# PM_proto_4.net
KiCad netlist of a schematic drawn in EAGLE
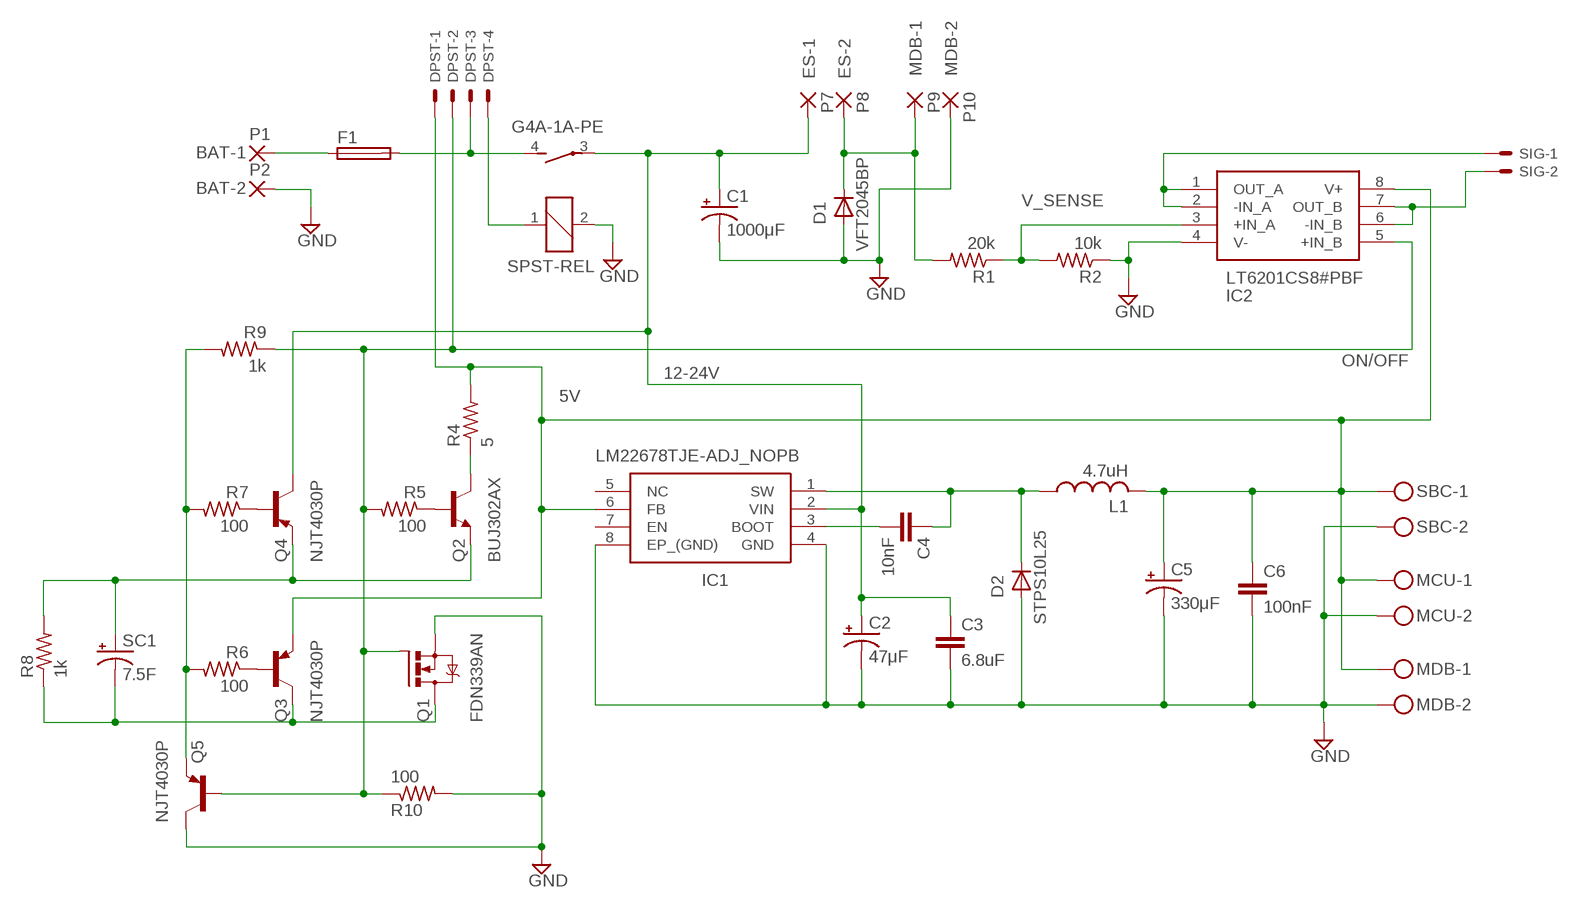
[diagram p0: schematic, sheet 1]

(export (version "E")
  (design (tool "Eeschema 10.0.6"))
  (components
    (comp (ref "C1")
      (value "1000μF")
      (footprint "eagle-import:E7,5-16")
      (libsource (lib "eagle-import") (part "CPOL-USE7.5-16"))
    )
    (comp (ref "C2")
      (value "47μF")
      (footprint "eagle-import:E2,5-6E")
      (libsource (lib "eagle-import") (part "CPOL-USE2,5-6E"))
    )
    (comp (ref "C3")
      (value "6.8uF")
      (footprint "eagle-import:C025-024X044")
      (libsource (lib "eagle-import") (part "C-EU025-024X044"))
    )
    (comp (ref "C4")
      (value "10nF")
      (footprint "eagle-import:C025-024X044")
      (libsource (lib "eagle-import") (part "C-EU025-024X044"))
    )
    (comp (ref "C5")
      (value "330μF")
      (footprint "eagle-import:E2,5-6E")
      (libsource (lib "eagle-import") (part "CPOL-USE2,5-6E"))
    )
    (comp (ref "C6")
      (value "100nF")
      (footprint "eagle-import:C025-024X044")
      (libsource (lib "eagle-import") (part "C-EU025-024X044"))
    )
    (comp (ref "D1")
      (value "VFT2045BP")
      (footprint "eagle-import:VFT2045BP")
      (libsource (lib "eagle-import") (part "VFT2045BP"))
    )
    (comp (ref "D2")
      (value "STPS10L25")
      (footprint "eagle-import:VFT2045BP")
      (libsource (lib "eagle-import") (part "VFT2045BP"))
    )
    (comp (ref "DPST")
      (value "JST-XH-04-PIN-LONG-PAD")
      (footprint "eagle-import:JST-XH-04-PACKAGE-LONG-PAD")
      (libsource (lib "eagle-import") (part "JST-XH-04-PIN-LONG-PAD"))
    )
    (comp (ref "F1")
      (value "0297015FUSE")
      (footprint "eagle-import:0297015HOLDER")
      (libsource (lib "eagle-import") (part "0297015FUSE"))
    )
    (comp (ref "IC1")
      (value "LM22678TJE-ADJ_NOPB")
      (footprint "eagle-import:LM22678TJEADJNOPB")
      (fields
        (field (name "ARROW_PART_NUMBER") "LM22678TJE-ADJ/NOPB")
        (field (name "RS_PART_NUMBER") "1625056")
      )
      (libsource (lib "eagle-import") (part "LM22678TJE-ADJ_NOPB"))
    )
    (comp (ref "IC2")
      (value "LT6201CS8#PBF")
      (footprint "eagle-import:SOIC127P599X175-8N")
      (fields (field (name "RS_PART_NUMBER") "5061072P"))
      (libsource (lib "eagle-import") (part "LT6201CS8#PBF"))
    )
    (comp (ref "L1")
      (value "4.7uH")
      (footprint "eagle-import:6000-XXXX-RC")
      (libsource (lib "eagle-import") (part "L-US6000-XXX-RC"))
    )
    (comp (ref "MCU")
      (value "MKDSN1,5/2-5,08")
      (footprint "eagle-import:MKDSN1,5_2-5,08")
      (libsource (lib "eagle-import") (part "MKDSN1,5/2-5,08"))
    )
    (comp (ref "MDB")
      (value "MKDSN1,5/2-5,08")
      (footprint "eagle-import:MKDSN1,5_2-5,08")
      (libsource (lib "eagle-import") (part "MKDSN1,5/2-5,08"))
    )
    (comp (ref "P1")
      (value "BAT-1")
      (footprint "eagle-import:1,6_0,8")
      (libsource (lib "eagle-import") (part "1,6/0,8"))
    )
    (comp (ref "P2")
      (value "BAT-2")
      (footprint "eagle-import:1,6_0,8")
      (libsource (lib "eagle-import") (part "1,6/0,8"))
    )
    (comp (ref "P7")
      (value "ES-1")
      (footprint "eagle-import:1,6_0,8")
      (libsource (lib "eagle-import") (part "1,6/0,8"))
    )
    (comp (ref "P8")
      (value "ES-2")
      (footprint "eagle-import:1,6_0,8")
      (libsource (lib "eagle-import") (part "1,6/0,8"))
    )
    (comp (ref "P9")
      (value "MDB-1")
      (footprint "eagle-import:1,6_0,8")
      (libsource (lib "eagle-import") (part "1,6/0,8"))
    )
    (comp (ref "P10")
      (value "MDB-2")
      (footprint "eagle-import:1,6_0,8")
      (libsource (lib "eagle-import") (part "1,6/0,8"))
    )
    (comp (ref "Q1")
      (value "FDN339AN")
      (footprint "eagle-import:TO220BH")
      (libsource (lib "eagle-import") (part "IRFZ48Z"))
    )
    (comp (ref "Q2")
      (value "BUJ302AX")
      (footprint "eagle-import:TO18")
      (libsource (lib "eagle-import") (part "2N706"))
    )
    (comp (ref "Q3")
      (value "NJT4030P")
      (footprint "eagle-import:TO18")
      (libsource (lib "eagle-import") (part "-PNP-TO18-EBCBC177B"))
    )
    (comp (ref "Q4")
      (value "NJT4030P")
      (footprint "eagle-import:TO18")
      (libsource (lib "eagle-import") (part "-PNP-TO18-EBCBC177B"))
    )
    (comp (ref "Q5")
      (value "NJT4030P")
      (footprint "eagle-import:TO18")
      (libsource (lib "eagle-import") (part "-PNP-TO18-EBCBC177B"))
    )
    (comp (ref "R1")
      (value "20k")
      (footprint "eagle-import:0204_7")
      (libsource (lib "eagle-import") (part "R-US_0204/7"))
    )
    (comp (ref "R2")
      (value "10k")
      (footprint "eagle-import:0204_7")
      (libsource (lib "eagle-import") (part "R-US_0204/7"))
    )
    (comp (ref "R4")
      (value "5")
      (footprint "eagle-import:TNP10SC10R0FE")
      (libsource (lib "eagle-import") (part "TNP10SC10R0FE"))
    )
    (comp (ref "R5")
      (value "100")
      (footprint "eagle-import:0204_7")
      (libsource (lib "eagle-import") (part "R-US_0204/7"))
    )
    (comp (ref "R6")
      (value "100")
      (footprint "eagle-import:0204_7")
      (libsource (lib "eagle-import") (part "R-US_0204/7"))
    )
    (comp (ref "R7")
      (value "100")
      (footprint "eagle-import:0204_7")
      (libsource (lib "eagle-import") (part "R-US_0204/7"))
    )
    (comp (ref "R8")
      (value "1k")
      (footprint "eagle-import:0204_7")
      (libsource (lib "eagle-import") (part "R-US_0204/7"))
    )
    (comp (ref "R9")
      (value "1k")
      (footprint "eagle-import:0204_7")
      (libsource (lib "eagle-import") (part "R-US_0204/7"))
    )
    (comp (ref "R10")
      (value "100")
      (footprint "eagle-import:0204_7")
      (libsource (lib "eagle-import") (part "R-US_0204/7"))
    )
    (comp (ref "SBC")
      (value "MKDSN1,5/2-5,08")
      (footprint "eagle-import:MKDSN1,5_2-5,08")
      (libsource (lib "eagle-import") (part "MKDSN1,5/2-5,08"))
    )
    (comp (ref "SC1")
      (value "7.5F")
      (footprint "eagle-import:SCMT32D755MRBB0")
      (libsource (lib "eagle-import") (part "SCMT32D755MRBB0"))
    )
    (comp (ref "SIG")
      (value "JST-XH-02-PIN-LONG-PAD")
      (footprint "eagle-import:JST-XH-02-PACKAGE-LONG-PAD")
      (libsource (lib "eagle-import") (part "JST-XH-02-PIN-LONG-PAD"))
    )
    (comp (ref "SPST-REL")
      (value "G4A-1A-PE")
      (footprint "eagle-import:G4A-1A-PE")
      (libsource (lib "eagle-import") (part "G4A-1A-PE"))
    )
  )
  (nets
    (net (code "1") (name "/5V") (class "Default")
      (node (ref "C5") (pin "+") (pinfunction "+_+") (pintype "passive"))
      (node (ref "C6") (pin "1") (pinfunction "1_1") (pintype "passive"))
      (node (ref "DPST") (pin "1") (pinfunction "S_1") (pintype "passive"))
      (node (ref "IC1") (pin "6") (pinfunction "FB_6") (pintype "input"))
      (node (ref "IC2") (pin "8") (pinfunction "V+_8") (pintype "power_in"))
      (node (ref "L1") (pin "2") (pinfunction "2_2") (pintype "passive"))
      (node (ref "MCU") (pin "1") (pinfunction "KL_1") (pintype "passive"))
      (node (ref "MDB") (pin "1") (pinfunction "KL_1") (pintype "passive"))
      (node (ref "Q3") (pin "1") (pinfunction "E_1") (pintype "passive"))
      (node (ref "R4") (pin "2") (pinfunction "2_2") (pintype "passive"))
      (node (ref "SBC") (pin "1") (pinfunction "KL_1") (pintype "passive"))
    )
    (net (code "2") (name "/12-24V") (class "Default")
      (node (ref "C1") (pin "+") (pinfunction "+_+") (pintype "passive"))
      (node (ref "C2") (pin "+") (pinfunction "+_+") (pintype "passive"))
      (node (ref "C3") (pin "1") (pinfunction "1_1") (pintype "passive"))
      (node (ref "IC1") (pin "2") (pinfunction "VIN_2") (pintype "power_in"))
      (node (ref "P7") (pin "1") (pinfunction "P_1") (pintype "passive"))
      (node (ref "Q4") (pin "3") (pinfunction "C_3") (pintype "passive"))
      (node (ref "SPST-REL") (pin "3") (pinfunction "P_3") (pintype "passive"))
    )
    (net (code "3") (name "/ON{slash}OFF") (class "Default")
      (node (ref "DPST") (pin "2") (pinfunction "S_2") (pintype "passive"))
      (node (ref "IC2") (pin "5") (pinfunction "+IN_B_5") (pintype "input"))
      (node (ref "Q1") (pin "G") (pinfunction "G_G") (pintype "passive"))
      (node (ref "Q5") (pin "2") (pinfunction "B_2") (pintype "passive"))
      (node (ref "R10") (pin "1") (pinfunction "1_1") (pintype "passive"))
      (node (ref "R5") (pin "2") (pinfunction "2_2") (pintype "passive"))
      (node (ref "R9") (pin "1") (pinfunction "1_1") (pintype "passive"))
    )
    (net (code "4") (name "/V_SENSE") (class "Default")
      (node (ref "IC2") (pin "3") (pinfunction "+IN_A_3") (pintype "input"))
      (node (ref "R1") (pin "1") (pinfunction "1_1") (pintype "passive"))
      (node (ref "R2") (pin "2") (pinfunction "2_2") (pintype "passive"))
    )
    (net (code "5") (name "GND") (class "Default")
      (node (ref "C1") (pin "-") (pinfunction "-_-") (pintype "passive"))
      (node (ref "C2") (pin "-") (pinfunction "-_-") (pintype "passive"))
      (node (ref "C3") (pin "2") (pinfunction "2_2") (pintype "passive"))
      (node (ref "C5") (pin "-") (pinfunction "-_-") (pintype "passive"))
      (node (ref "C6") (pin "2") (pinfunction "2_2") (pintype "passive"))
      (node (ref "D1") (pin "2") (pinfunction "A_2") (pintype "passive"))
      (node (ref "D2") (pin "2") (pinfunction "A_2") (pintype "passive"))
      (node (ref "IC1") (pin "4") (pinfunction "GND_4") (pintype "power_in"))
      (node (ref "IC1") (pin "8") (pinfunction "EP_(GND)_8") (pintype "power_in"))
      (node (ref "IC2") (pin "4") (pinfunction "V-_4") (pintype "power_in"))
      (node (ref "MCU") (pin "2") (pinfunction "KL_2") (pintype "passive"))
      (node (ref "MDB") (pin "2") (pinfunction "KL_2") (pintype "passive"))
      (node (ref "P10") (pin "1") (pinfunction "P_1") (pintype "passive"))
      (node (ref "P2") (pin "1") (pinfunction "P_1") (pintype "passive"))
      (node (ref "Q1") (pin "S") (pinfunction "S_S") (pintype "passive"))
      (node (ref "Q5") (pin "3") (pinfunction "C_3") (pintype "passive"))
      (node (ref "R10") (pin "2") (pinfunction "2_2") (pintype "passive"))
      (node (ref "R2") (pin "1") (pinfunction "1_1") (pintype "passive"))
      (node (ref "SBC") (pin "2") (pinfunction "KL_2") (pintype "passive"))
      (node (ref "SPST-REL") (pin "2") (pinfunction "2_2") (pintype "passive"))
    )
    (net (code "6") (name "Net-(D1-C)") (class "Default")
      (node (ref "D1") (pin "1") (pinfunction "C_1") (pintype "passive"))
      (node (ref "P8") (pin "1") (pinfunction "P_1") (pintype "passive"))
      (node (ref "P9") (pin "1") (pinfunction "P_1") (pintype "passive"))
      (node (ref "R1") (pin "2") (pinfunction "2_2") (pintype "passive"))
    )
    (net (code "7") (name "Net-(D2-C)") (class "Default")
      (node (ref "C4") (pin "1") (pinfunction "1_1") (pintype "passive"))
      (node (ref "D2") (pin "1") (pinfunction "C_1") (pintype "passive"))
      (node (ref "IC1") (pin "1") (pinfunction "SW_1") (pintype "power_in"))
      (node (ref "L1") (pin "1") (pinfunction "1_1") (pintype "passive"))
    )
    (net (code "8") (name "Net-(DPSTC-S)") (class "Default")
      (node (ref "DPST") (pin "3") (pinfunction "S_3") (pintype "passive"))
      (node (ref "F1") (pin "3") (pinfunction "2_3") (pintype "passive"))
      (node (ref "F1") (pin "4") (pinfunction "2_4") (pintype "passive"))
      (node (ref "SPST-REL") (pin "4") (pinfunction "S_4") (pintype "passive"))
    )
    (net (code "9") (name "Net-(DPSTD-S)") (class "Default")
      (node (ref "DPST") (pin "4") (pinfunction "S_4") (pintype "passive"))
      (node (ref "SPST-REL") (pin "1") (pinfunction "1_1") (pintype "passive"))
    )
    (net (code "10") (name "Net-(IC1-BOOT)") (class "Default")
      (node (ref "C4") (pin "2") (pinfunction "2_2") (pintype "passive"))
      (node (ref "IC1") (pin "3") (pinfunction "BOOT_3") (pintype "bidirectional"))
    )
    (net (code "11") (name "Net-(IC2--IN_A)") (class "Default")
      (node (ref "IC2") (pin "1") (pinfunction "OUT_A_1") (pintype "output"))
      (node (ref "IC2") (pin "2") (pinfunction "-IN_A_2") (pintype "input"))
      (node (ref "SIG") (pin "1") (pinfunction "S_1") (pintype "passive"))
    )
    (net (code "12") (name "Net-(IC2--IN_B)") (class "Default")
      (node (ref "IC2") (pin "6") (pinfunction "-IN_B_6") (pintype "input"))
      (node (ref "IC2") (pin "7") (pinfunction "OUT_B_7") (pintype "output"))
      (node (ref "SIG") (pin "2") (pinfunction "S_2") (pintype "passive"))
    )
    (net (code "13") (name "Net-(P1-P)") (class "Default")
      (node (ref "F1") (pin "1") (pinfunction "1_1") (pintype "passive"))
      (node (ref "F1") (pin "2") (pinfunction "1_2") (pintype "passive"))
      (node (ref "P1") (pin "1") (pinfunction "P_1") (pintype "passive"))
    )
    (net (code "14") (name "Net-(Q2-B)") (class "Default")
      (node (ref "Q2") (pin "2") (pinfunction "B_2") (pintype "passive"))
      (node (ref "R5") (pin "1") (pinfunction "1_1") (pintype "passive"))
    )
    (net (code "15") (name "Net-(Q2-C)") (class "Default")
      (node (ref "Q2") (pin "3") (pinfunction "C_3") (pintype "passive"))
      (node (ref "R4") (pin "1") (pinfunction "1_1") (pintype "passive"))
    )
    (net (code "16") (name "Net-(Q2-E)") (class "Default")
      (node (ref "Q2") (pin "1") (pinfunction "E_1") (pintype "passive"))
      (node (ref "Q4") (pin "1") (pinfunction "E_1") (pintype "passive"))
      (node (ref "R8") (pin "2") (pinfunction "2_2") (pintype "passive"))
      (node (ref "SC1") (pin "1") (pinfunction "+_1") (pintype "passive"))
    )
    (net (code "17") (name "Net-(Q3-B)") (class "Default")
      (node (ref "Q3") (pin "2") (pinfunction "B_2") (pintype "passive"))
      (node (ref "R6") (pin "1") (pinfunction "1_1") (pintype "passive"))
    )
    (net (code "18") (name "Net-(Q3-C)") (class "Default")
      (node (ref "Q1") (pin "D") (pinfunction "D_D") (pintype "passive"))
      (node (ref "Q3") (pin "3") (pinfunction "C_3") (pintype "passive"))
      (node (ref "R8") (pin "1") (pinfunction "1_1") (pintype "passive"))
      (node (ref "SC1") (pin "2") (pinfunction "-_2") (pintype "passive"))
    )
    (net (code "19") (name "Net-(Q4-B)") (class "Default")
      (node (ref "Q4") (pin "2") (pinfunction "B_2") (pintype "passive"))
      (node (ref "R7") (pin "1") (pinfunction "1_1") (pintype "passive"))
    )
    (net (code "20") (name "Net-(Q5-E)") (class "Default")
      (node (ref "Q5") (pin "1") (pinfunction "E_1") (pintype "passive"))
      (node (ref "R6") (pin "2") (pinfunction "2_2") (pintype "passive"))
      (node (ref "R7") (pin "2") (pinfunction "2_2") (pintype "passive"))
      (node (ref "R9") (pin "2") (pinfunction "2_2") (pintype "passive"))
    )
    (net (code "21") (name "unconnected-(IC1-EN-Pad7)") (class "Default")
      (node (ref "IC1") (pin "7") (pinfunction "EN_7") (pintype "input"))
    )
    (net (code "22") (name "unconnected-(IC1-NC-Pad5)") (class "Default")
      (node (ref "IC1") (pin "5") (pinfunction "NC_5") (pintype "no_connect"))
    )
  )
)
